# current_loop3.net
KiCad netlist of a schematic drawn in EAGLE
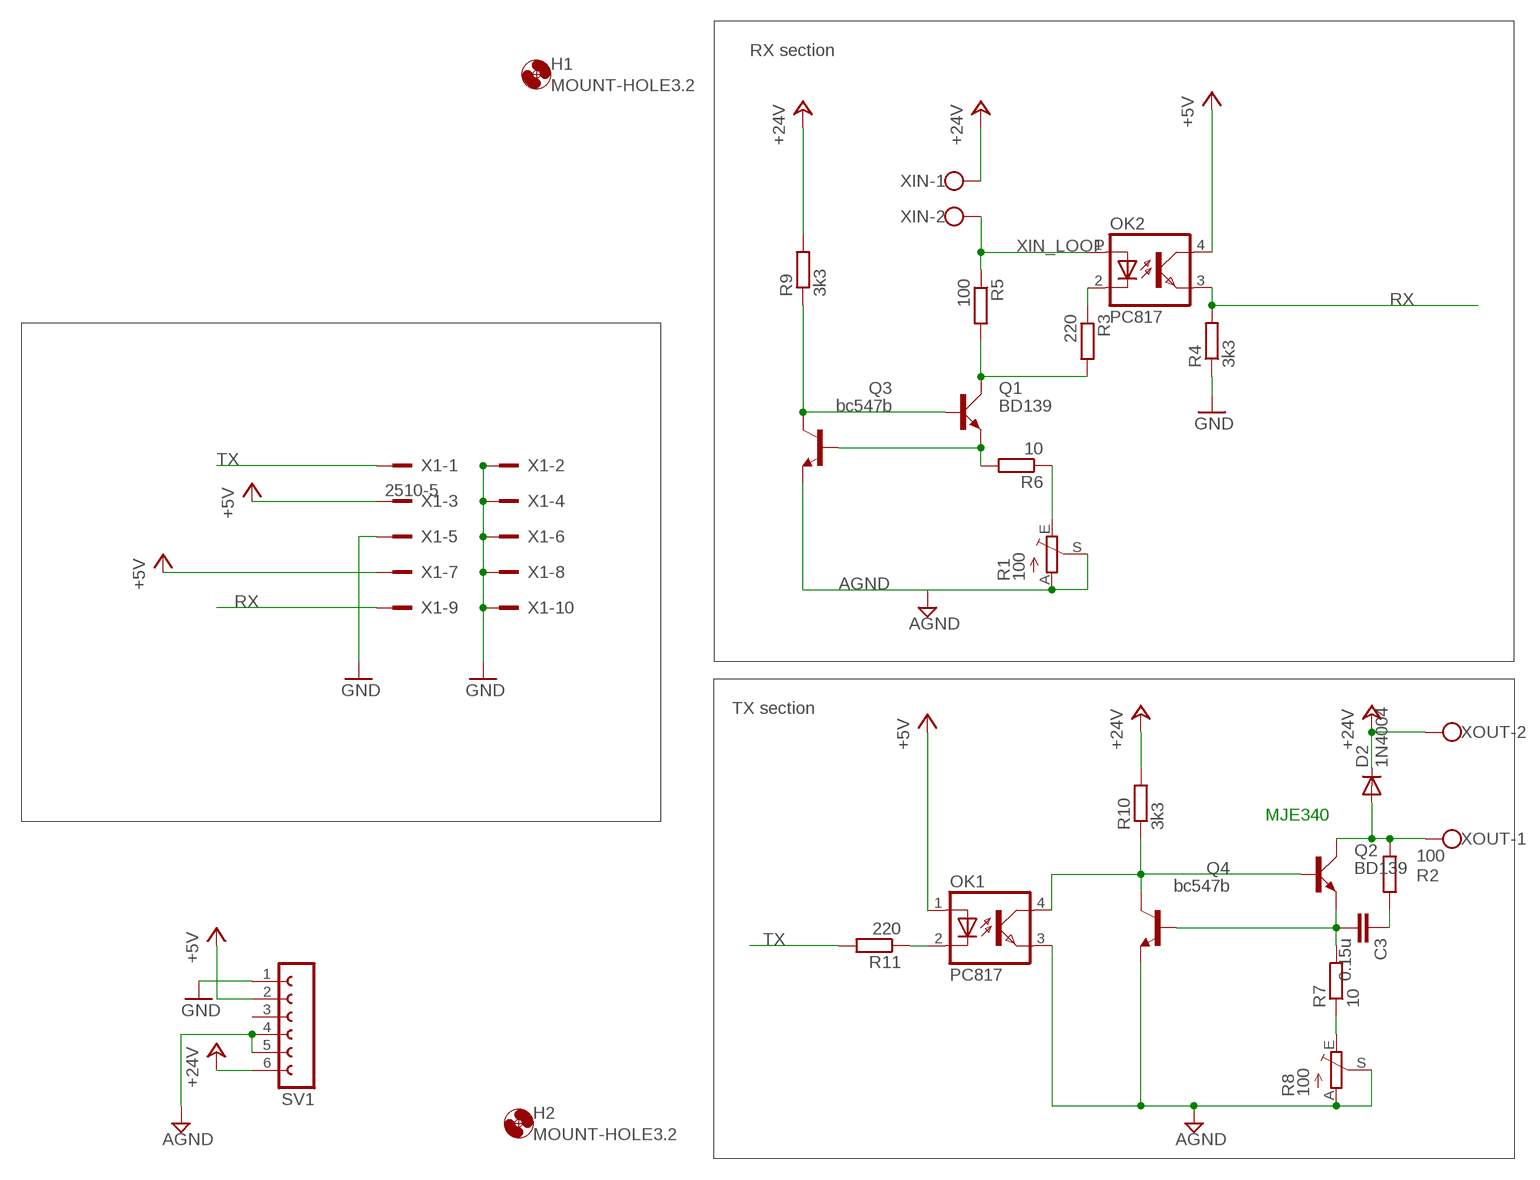
[diagram p0: schematic, sheet 1]

(export (version "E")
  (design (tool "Eeschema 10.0.6"))
  (components
    (comp (ref "C3")
      (value "0.15u")
      (footprint "eagle-import:C075-063X106")
      (libsource (lib "eagle-import") (part "C-EU075-063X106"))
    )
    (comp (ref "D2")
      (value "1N4004")
      (footprint "eagle-import:DO41-10")
      (libsource (lib "eagle-import") (part "1N4004"))
    )
    (comp (ref "H1")
      (value "MOUNT-HOLE3.2")
      (footprint "eagle-import:3,2")
      (libsource (lib "eagle-import") (part "MOUNT-HOLE3.2"))
    )
    (comp (ref "H2")
      (value "MOUNT-HOLE3.2")
      (footprint "eagle-import:3,2")
      (libsource (lib "eagle-import") (part "MOUNT-HOLE3.2"))
    )
    (comp (ref "OK1")
      (value "PC817")
      (footprint "eagle-import:DIL04")
      (fields (field (name "MPN") "PC817X4J000F"))
      (libsource (lib "eagle-import") (part "PC817"))
    )
    (comp (ref "OK2")
      (value "PC817")
      (footprint "eagle-import:DIL04")
      (fields (field (name "MPN") "PC817X4J000F"))
      (libsource (lib "eagle-import") (part "PC817"))
    )
    (comp (ref "Q1")
      (value "BD139")
      (footprint "eagle-import:TO126AV")
      (libsource (lib "eagle-import") (part "BD139"))
    )
    (comp (ref "Q2")
      (value "BD139")
      (footprint "eagle-import:TO126AV")
      (libsource (lib "eagle-import") (part "BD139"))
    )
    (comp (ref "Q3")
      (value "bc547b")
      (footprint "eagle-import:TO92-CBE")
      (libsource (lib "eagle-import") (part "-NPN-TO92-CBEBC547B"))
    )
    (comp (ref "Q4")
      (value "bc547b")
      (footprint "eagle-import:TO92-CBE")
      (libsource (lib "eagle-import") (part "-NPN-TO92-CBEBC547B"))
    )
    (comp (ref "R1")
      (value "100")
      (footprint "eagle-import:CA14H")
      (libsource (lib "eagle-import") (part "TRIM_EU-CA14H"))
    )
    (comp (ref "R2")
      (value "100")
      (footprint "eagle-import:0204V")
      (libsource (lib "eagle-import") (part "R-EU_0204/2V"))
    )
    (comp (ref "R3")
      (value "220")
      (footprint "eagle-import:0204V")
      (libsource (lib "eagle-import") (part "R-EU_0204/2V"))
    )
    (comp (ref "R4")
      (value "3k3")
      (footprint "eagle-import:0204V")
      (libsource (lib "eagle-import") (part "R-EU_0204/2V"))
    )
    (comp (ref "R5")
      (value "100")
      (footprint "eagle-import:0204V")
      (libsource (lib "eagle-import") (part "R-EU_0204/2V"))
    )
    (comp (ref "R6")
      (value "10")
      (footprint "eagle-import:0204_7")
      (libsource (lib "eagle-import") (part "R-EU_0204/7"))
    )
    (comp (ref "R7")
      (value "10")
      (footprint "eagle-import:0204V")
      (libsource (lib "eagle-import") (part "R-EU_0204/2V"))
    )
    (comp (ref "R8")
      (value "100")
      (footprint "eagle-import:CA14H")
      (libsource (lib "eagle-import") (part "TRIM_EU-CA14H"))
    )
    (comp (ref "R9")
      (value "3k3")
      (footprint "eagle-import:0204_7")
      (libsource (lib "eagle-import") (part "R-EU_0204/7"))
    )
    (comp (ref "R10")
      (value "3k3")
      (footprint "eagle-import:0204V")
      (libsource (lib "eagle-import") (part "R-EU_0204/2V"))
    )
    (comp (ref "R11")
      (value "220")
      (footprint "eagle-import:0204V")
      (libsource (lib "eagle-import") (part "R-EU_0204/2V"))
    )
    (comp (ref "SV1")
      (value "FE06-1")
      (footprint "eagle-import:FE06")
      (libsource (lib "eagle-import") (part "FE06-1"))
    )
    (comp (ref "X1")
      (value "2510-5")
      (footprint "eagle-import:PAK100_2500-5-10")
      (libsource (lib "eagle-import") (part "2510-5"))
    )
    (comp (ref "XIN")
      (value "W237-102")
      (footprint "eagle-import:W237-102")
      (fields (field (name "MPN") "237-102"))
      (libsource (lib "eagle-import") (part "W237-102"))
    )
    (comp (ref "XOUT")
      (value "W237-102")
      (footprint "eagle-import:W237-102")
      (fields (field (name "MPN") "237-102"))
      (libsource (lib "eagle-import") (part "W237-102"))
    )
  )
  (nets
    (net (code "1") (name "+5V") (class "Default")
      (node (ref "OK1") (pin "1") (pinfunction "A_1") (pintype "passive"))
      (node (ref "OK2") (pin "4") (pinfunction "COL_4") (pintype "passive"))
      (node (ref "SV1") (pin "2") (pinfunction "2_2") (pintype "passive"))
      (node (ref "X1") (pin "3") (pinfunction "KL_3") (pintype "passive"))
      (node (ref "X1") (pin "7") (pinfunction "KL_7") (pintype "passive"))
    )
    (net (code "2") (name "+24V") (class "Default")
      (node (ref "D2") (pin "C") (pinfunction "C_C") (pintype "passive"))
      (node (ref "R10") (pin "2") (pinfunction "2_2") (pintype "passive"))
      (node (ref "R9") (pin "2") (pinfunction "2_2") (pintype "passive"))
      (node (ref "SV1") (pin "6") (pinfunction "6_6") (pintype "passive"))
      (node (ref "XIN") (pin "1") (pinfunction "KL_1") (pintype "passive"))
      (node (ref "XOUT") (pin "2") (pinfunction "KL_2") (pintype "passive"))
    )
    (net (code "3") (name "/RX") (class "Default")
      (node (ref "OK2") (pin "3") (pinfunction "EMIT_3") (pintype "passive"))
      (node (ref "R4") (pin "2") (pinfunction "2_2") (pintype "passive"))
      (node (ref "X1") (pin "9") (pinfunction "KL_9") (pintype "passive"))
    )
    (net (code "4") (name "/TX") (class "Default")
      (node (ref "R11") (pin "2") (pinfunction "2_2") (pintype "passive"))
      (node (ref "X1") (pin "1") (pinfunction "KL_1") (pintype "passive"))
    )
    (net (code "5") (name "/XIN_LOOP") (class "Default")
      (node (ref "OK2") (pin "1") (pinfunction "A_1") (pintype "passive"))
      (node (ref "R5") (pin "1") (pinfunction "1_1") (pintype "passive"))
      (node (ref "XIN") (pin "2") (pinfunction "KL_2") (pintype "passive"))
    )
    (net (code "6") (name "AGND") (class "Default")
      (node (ref "OK1") (pin "3") (pinfunction "EMIT_3") (pintype "passive"))
      (node (ref "Q3") (pin "E") (pinfunction "E_E") (pintype "passive"))
      (node (ref "Q4") (pin "E") (pinfunction "E_E") (pintype "passive"))
      (node (ref "R1") (pin "A") (pinfunction "A_A") (pintype "passive"))
      (node (ref "R1") (pin "S") (pinfunction "S_S") (pintype "passive"))
      (node (ref "R8") (pin "A") (pinfunction "A_A") (pintype "passive"))
      (node (ref "R8") (pin "S") (pinfunction "S_S") (pintype "passive"))
      (node (ref "SV1") (pin "4") (pinfunction "4_4") (pintype "passive"))
      (node (ref "SV1") (pin "5") (pinfunction "5_5") (pintype "passive"))
    )
    (net (code "7") (name "GND") (class "Default")
      (node (ref "R4") (pin "1") (pinfunction "1_1") (pintype "passive"))
      (node (ref "SV1") (pin "1") (pinfunction "1_1") (pintype "passive"))
      (node (ref "X1") (pin "10") (pinfunction "KL_10") (pintype "passive"))
      (node (ref "X1") (pin "2") (pinfunction "KL_2") (pintype "passive"))
      (node (ref "X1") (pin "4") (pinfunction "KL_4") (pintype "passive"))
      (node (ref "X1") (pin "5") (pinfunction "KL_5") (pintype "passive"))
      (node (ref "X1") (pin "6") (pinfunction "KL_6") (pintype "passive"))
      (node (ref "X1") (pin "8") (pinfunction "KL_8") (pintype "passive"))
    )
    (net (code "8") (name "Net-(C3-Pad1)") (class "Default")
      (node (ref "C3") (pin "1") (pinfunction "1_1") (pintype "passive"))
      (node (ref "R2") (pin "1") (pinfunction "1_1") (pintype "passive"))
    )
    (net (code "9") (name "Net-(C3-Pad2)") (class "Default")
      (node (ref "C3") (pin "2") (pinfunction "2_2") (pintype "passive"))
      (node (ref "Q2") (pin "E") (pinfunction "E_E") (pintype "passive"))
      (node (ref "Q4") (pin "B") (pinfunction "B_B") (pintype "passive"))
      (node (ref "R7") (pin "2") (pinfunction "2_2") (pintype "passive"))
    )
    (net (code "10") (name "Net-(OK1-C)") (class "Default")
      (node (ref "OK1") (pin "2") (pinfunction "C_2") (pintype "passive"))
      (node (ref "R11") (pin "1") (pinfunction "1_1") (pintype "passive"))
    )
    (net (code "11") (name "Net-(OK1-COL)") (class "Default")
      (node (ref "OK1") (pin "4") (pinfunction "COL_4") (pintype "passive"))
      (node (ref "Q2") (pin "B") (pinfunction "B_B") (pintype "passive"))
      (node (ref "Q4") (pin "C") (pinfunction "C_C") (pintype "passive"))
      (node (ref "R10") (pin "1") (pinfunction "1_1") (pintype "passive"))
    )
    (net (code "12") (name "Net-(OK2-C)") (class "Default")
      (node (ref "OK2") (pin "2") (pinfunction "C_2") (pintype "passive"))
      (node (ref "R3") (pin "1") (pinfunction "1_1") (pintype "passive"))
    )
    (net (code "13") (name "Net-(Q1-PadB)") (class "Default")
      (node (ref "Q1") (pin "B") (pinfunction "B_B") (pintype "passive"))
      (node (ref "Q3") (pin "C") (pinfunction "C_C") (pintype "passive"))
      (node (ref "R9") (pin "1") (pinfunction "1_1") (pintype "passive"))
    )
    (net (code "14") (name "Net-(Q1-PadC)") (class "Default")
      (node (ref "Q1") (pin "C") (pinfunction "C_C") (pintype "passive"))
      (node (ref "R3") (pin "2") (pinfunction "2_2") (pintype "passive"))
      (node (ref "R5") (pin "2") (pinfunction "2_2") (pintype "passive"))
    )
    (net (code "15") (name "Net-(Q1-PadE)") (class "Default")
      (node (ref "Q1") (pin "E") (pinfunction "E_E") (pintype "passive"))
      (node (ref "Q3") (pin "B") (pinfunction "B_B") (pintype "passive"))
      (node (ref "R6") (pin "2") (pinfunction "2_2") (pintype "passive"))
    )
    (net (code "16") (name "Net-(R1-PadE)") (class "Default")
      (node (ref "R1") (pin "E") (pinfunction "E_E") (pintype "passive"))
      (node (ref "R6") (pin "1") (pinfunction "1_1") (pintype "passive"))
    )
    (net (code "17") (name "Net-(R7-Pad1)") (class "Default")
      (node (ref "R7") (pin "1") (pinfunction "1_1") (pintype "passive"))
      (node (ref "R8") (pin "E") (pinfunction "E_E") (pintype "passive"))
    )
    (net (code "18") (name "Net-(XOUTA-KL)") (class "Default")
      (node (ref "D2") (pin "A") (pinfunction "A_A") (pintype "passive"))
      (node (ref "Q2") (pin "C") (pinfunction "C_C") (pintype "passive"))
      (node (ref "R2") (pin "2") (pinfunction "2_2") (pintype "passive"))
      (node (ref "XOUT") (pin "1") (pinfunction "KL_1") (pintype "passive"))
    )
    (net (code "19") (name "unconnected-(SV1-Pad3)") (class "Default")
      (node (ref "SV1") (pin "3") (pinfunction "3_3") (pintype "passive"))
    )
  )
)
